# clack_beam_V.net
KiCad netlist of a schematic drawn in EAGLE
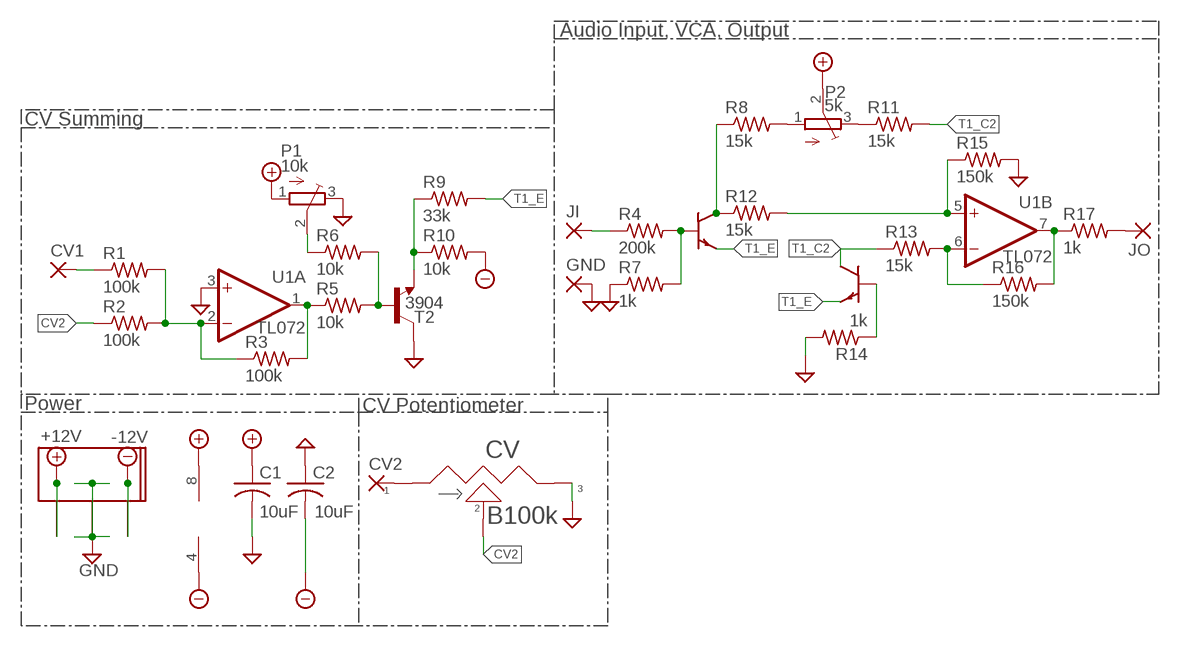
[diagram p0: schematic, sheet 1]

(export (version "E")
  (design (tool "Eeschema 10.0.6"))
  (components
    (comp (ref "C1")
      (value "10uF")
      (footprint "eagle-import:C1206")
      (libsource (lib "eagle-import") (part "C-USC1206"))
    )
    (comp (ref "C2")
      (value "10uF")
      (footprint "eagle-import:C1206")
      (libsource (lib "eagle-import") (part "C-USC1206"))
    )
    (comp (ref "CV")
      (value "B100k")
      (footprint "eagle-import:POT_9MM_SMD")
      (libsource (lib "eagle-import") (part "POT_9MM_SMD"))
    )
    (comp (ref "CV1")
      (value "WIREPADSMD1,27-254")
      (footprint "eagle-import:SMD1,27-2,54")
      (libsource (lib "eagle-import") (part "WIREPADSMD1,27-254"))
    )
    (comp (ref "CV2")
      (value "WIREPADSMD1,27-254")
      (footprint "eagle-import:SMD1,27-2,54")
      (libsource (lib "eagle-import") (part "WIREPADSMD1,27-254"))
    )
    (comp (ref "GND")
      (value "WIREPADSMD1,27-254")
      (footprint "eagle-import:SMD1,27-2,54")
      (libsource (lib "eagle-import") (part "WIREPADSMD1,27-254"))
    )
    (comp (ref "JI")
      (value "WIREPADSMD1,27-254")
      (footprint "eagle-import:SMD1,27-2,54")
      (libsource (lib "eagle-import") (part "WIREPADSMD1,27-254"))
    )
    (comp (ref "JO")
      (value "WIREPADSMD1,27-254")
      (footprint "eagle-import:SMD1,27-2,54")
      (libsource (lib "eagle-import") (part "WIREPADSMD1,27-254"))
    )
    (comp (ref "P1")
      (value "10k")
      (footprint "eagle-import:TC33X")
      (libsource (lib "eagle-import") (part "TRIMPOTTC33X"))
    )
    (comp (ref "P2")
      (value "5k")
      (footprint "eagle-import:TC33X")
      (libsource (lib "eagle-import") (part "TRIMPOTTC33X"))
    )
    (comp (ref "R1")
      (value "100k")
      (footprint "eagle-import:R0603")
      (libsource (lib "eagle-import") (part "R-US_R0603"))
    )
    (comp (ref "R2")
      (value "100k")
      (footprint "eagle-import:R0603")
      (libsource (lib "eagle-import") (part "R-US_R0603"))
    )
    (comp (ref "R3")
      (value "100k")
      (footprint "eagle-import:R0603")
      (libsource (lib "eagle-import") (part "R-US_R0603"))
    )
    (comp (ref "R4")
      (value "200k")
      (footprint "eagle-import:R0603")
      (libsource (lib "eagle-import") (part "R-US_R0603"))
    )
    (comp (ref "R5")
      (value "10k")
      (footprint "eagle-import:R0603")
      (libsource (lib "eagle-import") (part "R-US_R0603"))
    )
    (comp (ref "R6")
      (value "10k")
      (footprint "eagle-import:R0603")
      (libsource (lib "eagle-import") (part "R-US_R0603"))
    )
    (comp (ref "R7")
      (value "1k")
      (footprint "eagle-import:R0603")
      (libsource (lib "eagle-import") (part "R-US_R0603"))
    )
    (comp (ref "R8")
      (value "15k")
      (footprint "eagle-import:R0603")
      (libsource (lib "eagle-import") (part "R-US_R0603"))
    )
    (comp (ref "R9")
      (value "33k")
      (footprint "eagle-import:R0603")
      (libsource (lib "eagle-import") (part "R-US_R0603"))
    )
    (comp (ref "R10")
      (value "10k")
      (footprint "eagle-import:R0603")
      (libsource (lib "eagle-import") (part "R-US_R0603"))
    )
    (comp (ref "R11")
      (value "15k")
      (footprint "eagle-import:R0603")
      (libsource (lib "eagle-import") (part "R-US_R0603"))
    )
    (comp (ref "R12")
      (value "15k")
      (footprint "eagle-import:R0603")
      (libsource (lib "eagle-import") (part "R-US_R0603"))
    )
    (comp (ref "R13")
      (value "15k")
      (footprint "eagle-import:R0603")
      (libsource (lib "eagle-import") (part "R-US_R0603"))
    )
    (comp (ref "R14")
      (value "1k")
      (footprint "eagle-import:R0603")
      (libsource (lib "eagle-import") (part "R-US_R0603"))
    )
    (comp (ref "R15")
      (value "150k")
      (footprint "eagle-import:R0603")
      (libsource (lib "eagle-import") (part "R-US_R0603"))
    )
    (comp (ref "R16")
      (value "150k")
      (footprint "eagle-import:R0603")
      (libsource (lib "eagle-import") (part "R-US_R0603"))
    )
    (comp (ref "R17")
      (value "1k")
      (footprint "eagle-import:R0603")
      (libsource (lib "eagle-import") (part "R-US_R0603"))
    )
    (comp (ref "T1")
      (value "MBT3904DW1")
      (footprint "eagle-import:MBT3904DW1T1G")
      (libsource (lib "eagle-import") (part "MBT3904DW1"))
    )
    (comp (ref "T2")
      (value "3904")
      (footprint "eagle-import:SOT23-BEC")
      (libsource (lib "eagle-import") (part "-NPN-SOT23-BECMMBT3904LT1"))
    )
    (comp (ref "U$1")
      (value "EURO_POW_SMD")
      (footprint "eagle-import:EURO_POW_SMD")
      (libsource (lib "eagle-import") (part "EURO_POW_SMD"))
    )
    (comp (ref "U1")
      (value "TL072")
      (footprint "eagle-import:TSSOP-8")
      (libsource (lib "eagle-import") (part "TL072TSSOP"))
    )
  )
  (nets
    (net (code "1") (name "+12V") (class "Default")
      (node (ref "C1") (pin "1") (pinfunction "1_1") (pintype "passive"))
      (node (ref "P1") (pin "1") (pinfunction "A_1") (pintype "passive"))
      (node (ref "P2") (pin "2") (pinfunction "S_2") (pintype "passive"))
      (node (ref "U$1") (pin "P$10") (pinfunction "P$10_P$10") (pintype "bidirectional"))
      (node (ref "U$1") (pin "P$9") (pinfunction "P$9_P$9") (pintype "bidirectional"))
      (node (ref "U1") (pin "8") (pinfunction "V+_8") (pintype "power_in"))
    )
    (net (code "2") (name "-12V") (class "Default")
      (node (ref "C2") (pin "2") (pinfunction "2_2") (pintype "passive"))
      (node (ref "R10") (pin "2") (pinfunction "2_2") (pintype "passive"))
      (node (ref "U$1") (pin "P$1") (pinfunction "P$1_P$1") (pintype "bidirectional"))
      (node (ref "U$1") (pin "P$2") (pinfunction "P$2_P$2") (pintype "bidirectional"))
      (node (ref "U1") (pin "4") (pinfunction "V-_4") (pintype "power_in"))
    )
    (net (code "3") (name "CV2") (class "Default")
      (node (ref "CV") (pin "2") (pinfunction "2_2") (pintype "bidirectional"))
      (node (ref "R2") (pin "1") (pinfunction "1_1") (pintype "passive"))
    )
    (net (code "4") (name "GND") (class "Default")
      (node (ref "C1") (pin "2") (pinfunction "2_2") (pintype "passive"))
      (node (ref "C2") (pin "1") (pinfunction "1_1") (pintype "passive"))
      (node (ref "CV") (pin "3") (pinfunction "3_3") (pintype "bidirectional"))
      (node (ref "GND") (pin "1") (pinfunction "P_1") (pintype "passive"))
      (node (ref "P1") (pin "3") (pinfunction "E_3") (pintype "passive"))
      (node (ref "R14") (pin "2") (pinfunction "2_2") (pintype "passive"))
      (node (ref "R15") (pin "2") (pinfunction "2_2") (pintype "passive"))
      (node (ref "R7") (pin "1") (pinfunction "1_1") (pintype "passive"))
      (node (ref "T2") (pin "C") (pinfunction "C_C") (pintype "passive"))
      (node (ref "U$1") (pin "P$3") (pinfunction "P$3_P$3") (pintype "bidirectional"))
      (node (ref "U$1") (pin "P$4") (pinfunction "P$4_P$4") (pintype "bidirectional"))
      (node (ref "U$1") (pin "P$5") (pinfunction "P$5_P$5") (pintype "bidirectional"))
      (node (ref "U$1") (pin "P$6") (pinfunction "P$6_P$6") (pintype "bidirectional"))
      (node (ref "U$1") (pin "P$7") (pinfunction "P$7_P$7") (pintype "bidirectional"))
      (node (ref "U$1") (pin "P$8") (pinfunction "P$8_P$8") (pintype "bidirectional"))
      (node (ref "U1") (pin "3") (pinfunction "+IN_3") (pintype "input"))
    )
    (net (code "5") (name "Net-(CV1-P)") (class "Default")
      (node (ref "CV1") (pin "1") (pinfunction "P_1") (pintype "passive"))
      (node (ref "R1") (pin "1") (pinfunction "1_1") (pintype "passive"))
    )
    (net (code "6") (name "Net-(CV2-P)") (class "Default")
      (node (ref "CV") (pin "1") (pinfunction "1_1") (pintype "bidirectional"))
      (node (ref "CV2") (pin "1") (pinfunction "P_1") (pintype "passive"))
    )
    (net (code "7") (name "Net-(JI-P)") (class "Default")
      (node (ref "JI") (pin "1") (pinfunction "P_1") (pintype "passive"))
      (node (ref "R4") (pin "1") (pinfunction "1_1") (pintype "passive"))
    )
    (net (code "8") (name "Net-(JO-P)") (class "Default")
      (node (ref "JO") (pin "1") (pinfunction "P_1") (pintype "passive"))
      (node (ref "R17") (pin "2") (pinfunction "2_2") (pintype "passive"))
    )
    (net (code "9") (name "Net-(P1-S)") (class "Default")
      (node (ref "P1") (pin "2") (pinfunction "S_2") (pintype "passive"))
      (node (ref "R6") (pin "1") (pinfunction "1_1") (pintype "passive"))
    )
    (net (code "10") (name "Net-(P2-A)") (class "Default")
      (node (ref "P2") (pin "1") (pinfunction "A_1") (pintype "passive"))
      (node (ref "R8") (pin "2") (pinfunction "2_2") (pintype "passive"))
    )
    (net (code "11") (name "Net-(P2-E)") (class "Default")
      (node (ref "P2") (pin "3") (pinfunction "E_3") (pintype "passive"))
      (node (ref "R11") (pin "1") (pinfunction "1_1") (pintype "passive"))
    )
    (net (code "12") (name "Net-(R5-Pad2)") (class "Default")
      (node (ref "R5") (pin "2") (pinfunction "2_2") (pintype "passive"))
      (node (ref "R6") (pin "2") (pinfunction "2_2") (pintype "passive"))
      (node (ref "T2") (pin "B") (pinfunction "B_B") (pintype "passive"))
    )
    (net (code "13") (name "Net-(R10-Pad1)") (class "Default")
      (node (ref "R10") (pin "1") (pinfunction "1_1") (pintype "passive"))
      (node (ref "R9") (pin "1") (pinfunction "1_1") (pintype "passive"))
      (node (ref "T2") (pin "E") (pinfunction "E_E") (pintype "passive"))
    )
    (net (code "14") (name "Net-(T1A-B)") (class "Default")
      (node (ref "R4") (pin "2") (pinfunction "2_2") (pintype "passive"))
      (node (ref "R7") (pin "2") (pinfunction "2_2") (pintype "passive"))
      (node (ref "T1") (pin "5") (pinfunction "B_5") (pintype "bidirectional"))
    )
    (net (code "15") (name "Net-(T1A-C)") (class "Default")
      (node (ref "R12") (pin "1") (pinfunction "1_1") (pintype "passive"))
      (node (ref "R8") (pin "1") (pinfunction "1_1") (pintype "passive"))
      (node (ref "T1") (pin "3") (pinfunction "C_3") (pintype "bidirectional"))
    )
    (net (code "16") (name "Net-(T1B-B)") (class "Default")
      (node (ref "R14") (pin "1") (pinfunction "1_1") (pintype "passive"))
      (node (ref "T1") (pin "2") (pinfunction "B_2") (pintype "bidirectional"))
    )
    (net (code "17") (name "Net-(U1A--IN)") (class "Default")
      (node (ref "R1") (pin "2") (pinfunction "2_2") (pintype "passive"))
      (node (ref "R2") (pin "2") (pinfunction "2_2") (pintype "passive"))
      (node (ref "R3") (pin "1") (pinfunction "1_1") (pintype "passive"))
      (node (ref "U1") (pin "2") (pinfunction "-IN_2") (pintype "input"))
    )
    (net (code "18") (name "Net-(U1A-OUT)") (class "Default")
      (node (ref "R3") (pin "2") (pinfunction "2_2") (pintype "passive"))
      (node (ref "R5") (pin "1") (pinfunction "1_1") (pintype "passive"))
      (node (ref "U1") (pin "1") (pinfunction "OUT_1") (pintype "output"))
    )
    (net (code "19") (name "Net-(U1B-+IN)") (class "Default")
      (node (ref "R12") (pin "2") (pinfunction "2_2") (pintype "passive"))
      (node (ref "R15") (pin "1") (pinfunction "1_1") (pintype "passive"))
      (node (ref "U1") (pin "5") (pinfunction "+IN_5") (pintype "input"))
    )
    (net (code "20") (name "Net-(U1B--IN)") (class "Default")
      (node (ref "R13") (pin "2") (pinfunction "2_2") (pintype "passive"))
      (node (ref "R16") (pin "1") (pinfunction "1_1") (pintype "passive"))
      (node (ref "U1") (pin "6") (pinfunction "-IN_6") (pintype "input"))
    )
    (net (code "21") (name "Net-(U1B-OUT)") (class "Default")
      (node (ref "R16") (pin "2") (pinfunction "2_2") (pintype "passive"))
      (node (ref "R17") (pin "1") (pinfunction "1_1") (pintype "passive"))
      (node (ref "U1") (pin "7") (pinfunction "OUT_7") (pintype "output"))
    )
    (net (code "22") (name "T1_C2") (class "Default")
      (node (ref "R11") (pin "2") (pinfunction "2_2") (pintype "passive"))
      (node (ref "R13") (pin "1") (pinfunction "1_1") (pintype "passive"))
      (node (ref "T1") (pin "6") (pinfunction "C_6") (pintype "bidirectional"))
    )
    (net (code "23") (name "T1_E") (class "Default")
      (node (ref "R9") (pin "2") (pinfunction "2_2") (pintype "passive"))
      (node (ref "T1") (pin "1") (pinfunction "E_1") (pintype "bidirectional"))
      (node (ref "T1") (pin "4") (pinfunction "E_4") (pintype "bidirectional"))
    )
  )
)
